# GloveBoard.net
KiCad netlist of a schematic drawn in EAGLE
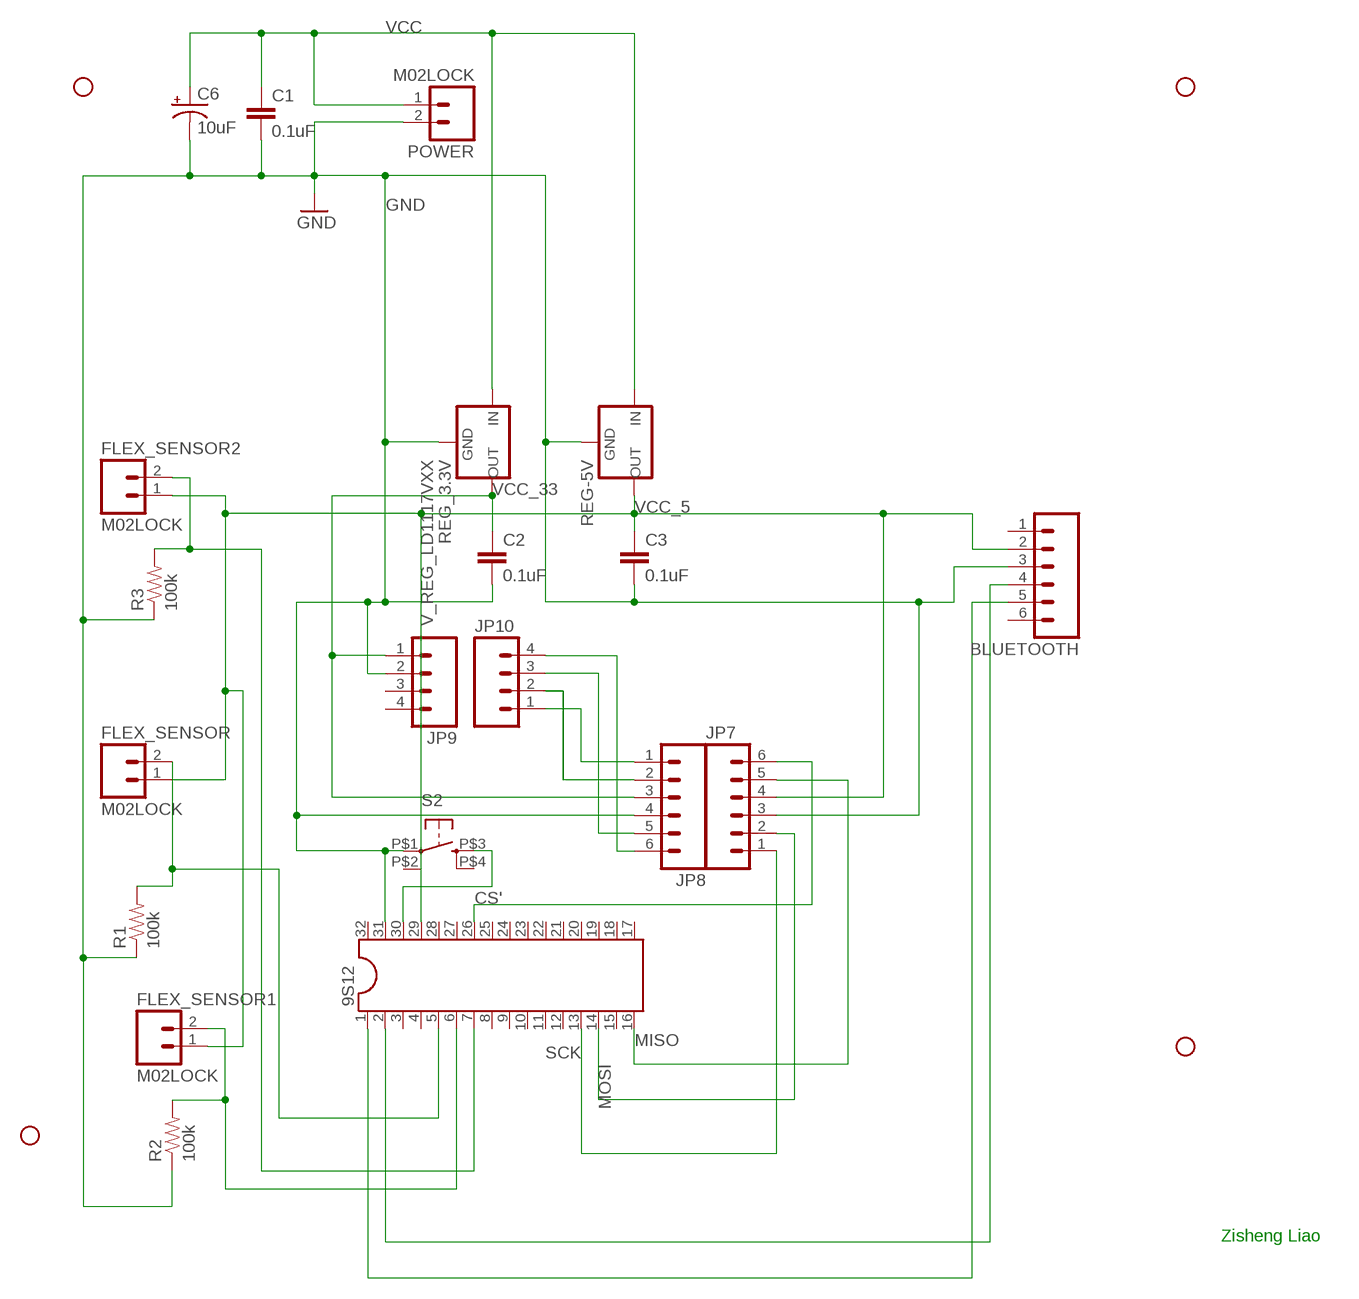
[diagram p0: schematic, sheet 1]

(export (version "E")
  (design (tool "Eeschema 10.0.6"))
  (components
    (comp (ref "9S12")
      (value "DIL32")
      (footprint "eagle-import:DIL32")
      (libsource (lib "eagle-import") (part "DIL32"))
    )
    (comp (ref "BLUETOOTH")
      (value "M06LOCK_LONGPADS")
      (footprint "eagle-import:1X06_LOCK_LONGPADS")
      (libsource (lib "eagle-import") (part "M06LOCK_LONGPADS"))
    )
    (comp (ref "C1")
      (value "0.1uF")
      (footprint "eagle-import:CAP-PTH-SMALL-KIT")
      (libsource (lib "eagle-import") (part "0.1UF-50V-20%(PTH)KIT-EZ"))
    )
    (comp (ref "C2")
      (value "0.1uF")
      (footprint "eagle-import:CAP-PTH-SMALL-KIT")
      (libsource (lib "eagle-import") (part "0.1UF-50V-20%(PTH)KIT-EZ"))
    )
    (comp (ref "C3")
      (value "0.1uF")
      (footprint "eagle-import:CAP-PTH-SMALL-KIT")
      (libsource (lib "eagle-import") (part "0.1UF-50V-20%(PTH)KIT-EZ"))
    )
    (comp (ref "C6")
      (value "10uF")
      (footprint "eagle-import:CPOL-RADIAL-10UF-25V")
      (libsource (lib "eagle-import") (part "CAP_POLPTH2"))
    )
    (comp (ref "FLEX_SENSOR")
      (value "M02LOCK")
      (footprint "eagle-import:1X02_LOCK")
      (libsource (lib "eagle-import") (part "M02LOCK"))
    )
    (comp (ref "FLEX_SENSOR1")
      (value "M02LOCK")
      (footprint "eagle-import:1X02_LOCK")
      (libsource (lib "eagle-import") (part "M02LOCK"))
    )
    (comp (ref "FLEX_SENSOR2")
      (value "M02LOCK")
      (footprint "eagle-import:1X02_LOCK")
      (libsource (lib "eagle-import") (part "M02LOCK"))
    )
    (comp (ref "JP7")
      (value "M06LOCK_LONGPADS")
      (footprint "eagle-import:1X06_LOCK_LONGPADS")
      (libsource (lib "eagle-import") (part "M06LOCK_LONGPADS"))
    )
    (comp (ref "JP8")
      (value "M06LOCK_LONGPADS")
      (footprint "eagle-import:1X06_LOCK_LONGPADS")
      (libsource (lib "eagle-import") (part "M06LOCK_LONGPADS"))
    )
    (comp (ref "JP9")
      (value "M04PTH")
      (footprint "eagle-import:1X04")
      (libsource (lib "eagle-import") (part "M04PTH"))
    )
    (comp (ref "JP10")
      (value "M04PTH")
      (footprint "eagle-import:1X04")
      (libsource (lib "eagle-import") (part "M04PTH"))
    )
    (comp (ref "POWER")
      (value "M02LOCK")
      (footprint "eagle-import:1X02_LOCK")
      (libsource (lib "eagle-import") (part "M02LOCK"))
    )
    (comp (ref "R1")
      (value "100k")
      (footprint "eagle-import:AXIAL-0.3-KIT")
      (libsource (lib "eagle-import") (part "10KOHM1/6W5%(PTH)KIT"))
    )
    (comp (ref "R2")
      (value "100k")
      (footprint "eagle-import:AXIAL-0.3-KIT")
      (libsource (lib "eagle-import") (part "10KOHM1/6W5%(PTH)KIT"))
    )
    (comp (ref "R3")
      (value "100k")
      (footprint "eagle-import:AXIAL-0.3-KIT")
      (libsource (lib "eagle-import") (part "10KOHM1/6W5%(PTH)KIT"))
    )
    (comp (ref "REG-5V")
      (value "V_REG_78XX-TO-220")
      (footprint "eagle-import:TO-220-ALT")
      (libsource (lib "eagle-import") (part "V_REG_78XX-TO-220"))
    )
    (comp (ref "REG_3.3V")
      (value "V_REG_LD1117VXX")
      (footprint "eagle-import:78XXL")
      (libsource (lib "eagle-import") (part "V_REG_LD1117VXX"))
    )
    (comp (ref "S2")
      (value "TAC_SWITCHKSA_SEALED")
      (footprint "eagle-import:KSA_SEALED_TAC_SWITCH")
      (libsource (lib "eagle-import") (part "TAC_SWITCHKSA_SEALED"))
    )
    (comp (ref "STANDOFF1")
      (value "STAND-OFF")
      (footprint "eagle-import:STAND-OFF")
      (libsource (lib "eagle-import") (part "STAND-OFF"))
    )
    (comp (ref "STANDOFF2")
      (value "STAND-OFF")
      (footprint "eagle-import:STAND-OFF")
      (libsource (lib "eagle-import") (part "STAND-OFF"))
    )
    (comp (ref "STANDOFF3")
      (value "STAND-OFF")
      (footprint "eagle-import:STAND-OFF")
      (libsource (lib "eagle-import") (part "STAND-OFF"))
    )
    (comp (ref "STANDOFF4")
      (value "STAND-OFF")
      (footprint "eagle-import:STAND-OFF")
      (libsource (lib "eagle-import") (part "STAND-OFF"))
    )
  )
  (nets
    (net (code "1") (name "/CS'") (class "Default")
      (node (ref "9S12") (pin "26") (pinfunction "26_26") (pintype "passive"))
      (node (ref "JP7") (pin "6") (pinfunction "6_6") (pintype "passive"))
    )
    (net (code "2") (name "/MISO") (class "Default")
      (node (ref "9S12") (pin "16") (pinfunction "16_16") (pintype "passive"))
      (node (ref "JP7") (pin "5") (pinfunction "5_5") (pintype "passive"))
    )
    (net (code "3") (name "/MOSI") (class "Default")
      (node (ref "9S12") (pin "14") (pinfunction "14_14") (pintype "passive"))
      (node (ref "JP7") (pin "2") (pinfunction "2_2") (pintype "passive"))
    )
    (net (code "4") (name "/SCK") (class "Default")
      (node (ref "9S12") (pin "13") (pinfunction "13_13") (pintype "passive"))
      (node (ref "JP7") (pin "1") (pinfunction "1_1") (pintype "passive"))
    )
    (net (code "5") (name "/VCC") (class "Default")
      (node (ref "C1") (pin "1") (pinfunction "1_1") (pintype "passive"))
      (node (ref "C6") (pin "1") (pinfunction "+_1") (pintype "passive"))
      (node (ref "POWER") (pin "1") (pinfunction "1_1") (pintype "passive"))
      (node (ref "REG-5V") (pin "IN") (pinfunction "IN_IN") (pintype "input"))
      (node (ref "REG_3.3V") (pin "OUT") (pinfunction "IN_OUT") (pintype "input"))
    )
    (net (code "6") (name "/VCC_5") (class "Default")
      (node (ref "9S12") (pin "29") (pinfunction "29_29") (pintype "passive"))
      (node (ref "BLUETOOTH") (pin "2") (pinfunction "2_2") (pintype "passive"))
      (node (ref "C3") (pin "1") (pinfunction "1_1") (pintype "passive"))
      (node (ref "FLEX_SENSOR") (pin "1") (pinfunction "1_1") (pintype "passive"))
      (node (ref "FLEX_SENSOR1") (pin "1") (pinfunction "1_1") (pintype "passive"))
      (node (ref "FLEX_SENSOR2") (pin "1") (pinfunction "1_1") (pintype "passive"))
      (node (ref "JP7") (pin "4") (pinfunction "4_4") (pintype "passive"))
      (node (ref "REG-5V") (pin "OUT") (pinfunction "OUT_OUT") (pintype "output"))
    )
    (net (code "7") (name "/VCC_33") (class "Default")
      (node (ref "C2") (pin "1") (pinfunction "1_1") (pintype "passive"))
      (node (ref "JP8") (pin "3") (pinfunction "3_3") (pintype "passive"))
      (node (ref "JP9") (pin "1") (pinfunction "1_1") (pintype "passive"))
      (node (ref "REG_3.3V") (pin "GND") (pinfunction "OUT_GND") (pintype "output"))
    )
    (net (code "8") (name "GND") (class "Default")
      (node (ref "9S12") (pin "31") (pinfunction "31_31") (pintype "passive"))
      (node (ref "BLUETOOTH") (pin "3") (pinfunction "3_3") (pintype "passive"))
      (node (ref "C1") (pin "2") (pinfunction "2_2") (pintype "passive"))
      (node (ref "C2") (pin "2") (pinfunction "2_2") (pintype "passive"))
      (node (ref "C3") (pin "2") (pinfunction "2_2") (pintype "passive"))
      (node (ref "C6") (pin "2") (pinfunction "-_2") (pintype "passive"))
      (node (ref "JP7") (pin "3") (pinfunction "3_3") (pintype "passive"))
      (node (ref "JP8") (pin "4") (pinfunction "4_4") (pintype "passive"))
      (node (ref "JP9") (pin "2") (pinfunction "2_2") (pintype "passive"))
      (node (ref "POWER") (pin "2") (pinfunction "2_2") (pintype "passive"))
      (node (ref "R1") (pin "P$1") (pinfunction "1_P$1") (pintype "passive"))
      (node (ref "R2") (pin "P$1") (pinfunction "1_P$1") (pintype "passive"))
      (node (ref "R3") (pin "P$1") (pinfunction "1_P$1") (pintype "passive"))
      (node (ref "REG-5V") (pin "GND") (pinfunction "GND_GND") (pintype "input"))
      (node (ref "REG_3.3V") (pin "IN") (pinfunction "GND_IN") (pintype "input"))
      (node (ref "S2") (pin "P$1") (pinfunction "1_P$1") (pintype "passive"))
    )
    (net (code "9") (name "Net-(9S12-Pad1)") (class "Default")
      (node (ref "9S12") (pin "1") (pinfunction "1_1") (pintype "passive"))
      (node (ref "BLUETOOTH") (pin "5") (pinfunction "5_5") (pintype "passive"))
    )
    (net (code "10") (name "Net-(9S12-Pad2)") (class "Default")
      (node (ref "9S12") (pin "2") (pinfunction "2_2") (pintype "passive"))
      (node (ref "BLUETOOTH") (pin "4") (pinfunction "4_4") (pintype "passive"))
    )
    (net (code "11") (name "Net-(JP10-Pad1)") (class "Default")
      (node (ref "JP10") (pin "1") (pinfunction "1_1") (pintype "passive"))
      (node (ref "JP8") (pin "1") (pinfunction "1_1") (pintype "passive"))
    )
    (net (code "12") (name "Net-(JP10-Pad2)") (class "Default")
      (node (ref "JP10") (pin "2") (pinfunction "2_2") (pintype "passive"))
      (node (ref "JP8") (pin "2") (pinfunction "2_2") (pintype "passive"))
    )
    (net (code "13") (name "Net-(JP10-Pad3)") (class "Default")
      (node (ref "JP10") (pin "3") (pinfunction "3_3") (pintype "passive"))
      (node (ref "JP8") (pin "5") (pinfunction "5_5") (pintype "passive"))
    )
    (net (code "14") (name "Net-(JP10-Pad4)") (class "Default")
      (node (ref "JP10") (pin "4") (pinfunction "4_4") (pintype "passive"))
      (node (ref "JP8") (pin "6") (pinfunction "6_6") (pintype "passive"))
    )
    (net (code "15") (name "Net-(R1-2)") (class "Default")
      (node (ref "9S12") (pin "5") (pinfunction "5_5") (pintype "passive"))
      (node (ref "FLEX_SENSOR") (pin "2") (pinfunction "2_2") (pintype "passive"))
      (node (ref "R1") (pin "P$2") (pinfunction "2_P$2") (pintype "passive"))
    )
    (net (code "16") (name "Net-(R2-2)") (class "Default")
      (node (ref "9S12") (pin "6") (pinfunction "6_6") (pintype "passive"))
      (node (ref "FLEX_SENSOR1") (pin "2") (pinfunction "2_2") (pintype "passive"))
      (node (ref "R2") (pin "P$2") (pinfunction "2_P$2") (pintype "passive"))
    )
    (net (code "17") (name "Net-(R3-2)") (class "Default")
      (node (ref "9S12") (pin "7") (pinfunction "7_7") (pintype "passive"))
      (node (ref "FLEX_SENSOR2") (pin "2") (pinfunction "2_2") (pintype "passive"))
      (node (ref "R3") (pin "P$2") (pinfunction "2_P$2") (pintype "passive"))
    )
    (net (code "18") (name "Net-(S2-3)") (class "Default")
      (node (ref "9S12") (pin "30") (pinfunction "30_30") (pintype "passive"))
      (node (ref "S2") (pin "P$3") (pinfunction "3_P$3") (pintype "passive"))
    )
    (net (code "19") (name "unconnected-(9S12-Pad3)") (class "Default")
      (node (ref "9S12") (pin "3") (pinfunction "3_3") (pintype "passive"))
    )
    (net (code "20") (name "unconnected-(9S12-Pad4)") (class "Default")
      (node (ref "9S12") (pin "4") (pinfunction "4_4") (pintype "passive"))
    )
    (net (code "21") (name "unconnected-(9S12-Pad8)") (class "Default")
      (node (ref "9S12") (pin "8") (pinfunction "8_8") (pintype "passive"))
    )
    (net (code "22") (name "unconnected-(9S12-Pad9)") (class "Default")
      (node (ref "9S12") (pin "9") (pinfunction "9_9") (pintype "passive"))
    )
    (net (code "23") (name "unconnected-(9S12-Pad10)") (class "Default")
      (node (ref "9S12") (pin "10") (pinfunction "10_10") (pintype "passive"))
    )
    (net (code "24") (name "unconnected-(9S12-Pad11)") (class "Default")
      (node (ref "9S12") (pin "11") (pinfunction "11_11") (pintype "passive"))
    )
    (net (code "25") (name "unconnected-(9S12-Pad12)") (class "Default")
      (node (ref "9S12") (pin "12") (pinfunction "12_12") (pintype "passive"))
    )
    (net (code "26") (name "unconnected-(9S12-Pad15)") (class "Default")
      (node (ref "9S12") (pin "15") (pinfunction "15_15") (pintype "passive"))
    )
    (net (code "27") (name "unconnected-(9S12-Pad17)") (class "Default")
      (node (ref "9S12") (pin "17") (pinfunction "17_17") (pintype "passive"))
    )
    (net (code "28") (name "unconnected-(9S12-Pad18)") (class "Default")
      (node (ref "9S12") (pin "18") (pinfunction "18_18") (pintype "passive"))
    )
    (net (code "29") (name "unconnected-(9S12-Pad19)") (class "Default")
      (node (ref "9S12") (pin "19") (pinfunction "19_19") (pintype "passive"))
    )
    (net (code "30") (name "unconnected-(9S12-Pad20)") (class "Default")
      (node (ref "9S12") (pin "20") (pinfunction "20_20") (pintype "passive"))
    )
    (net (code "31") (name "unconnected-(9S12-Pad21)") (class "Default")
      (node (ref "9S12") (pin "21") (pinfunction "21_21") (pintype "passive"))
    )
    (net (code "32") (name "unconnected-(9S12-Pad22)") (class "Default")
      (node (ref "9S12") (pin "22") (pinfunction "22_22") (pintype "passive"))
    )
    (net (code "33") (name "unconnected-(9S12-Pad23)") (class "Default")
      (node (ref "9S12") (pin "23") (pinfunction "23_23") (pintype "passive"))
    )
    (net (code "34") (name "unconnected-(9S12-Pad24)") (class "Default")
      (node (ref "9S12") (pin "24") (pinfunction "24_24") (pintype "passive"))
    )
    (net (code "35") (name "unconnected-(9S12-Pad25)") (class "Default")
      (node (ref "9S12") (pin "25") (pinfunction "25_25") (pintype "passive"))
    )
    (net (code "36") (name "unconnected-(9S12-Pad27)") (class "Default")
      (node (ref "9S12") (pin "27") (pinfunction "27_27") (pintype "passive"))
    )
    (net (code "37") (name "unconnected-(9S12-Pad28)") (class "Default")
      (node (ref "9S12") (pin "28") (pinfunction "28_28") (pintype "passive"))
    )
    (net (code "38") (name "unconnected-(9S12-Pad32)") (class "Default")
      (node (ref "9S12") (pin "32") (pinfunction "32_32") (pintype "passive"))
    )
    (net (code "39") (name "unconnected-(BLUETOOTH-Pad1)") (class "Default")
      (node (ref "BLUETOOTH") (pin "1") (pinfunction "1_1") (pintype "passive"))
    )
    (net (code "40") (name "unconnected-(BLUETOOTH-Pad6)") (class "Default")
      (node (ref "BLUETOOTH") (pin "6") (pinfunction "6_6") (pintype "passive"))
    )
    (net (code "41") (name "unconnected-(JP9-Pad3)") (class "Default")
      (node (ref "JP9") (pin "3") (pinfunction "3_3") (pintype "passive"))
    )
    (net (code "42") (name "unconnected-(JP9-Pad4)") (class "Default")
      (node (ref "JP9") (pin "4") (pinfunction "4_4") (pintype "passive"))
    )
    (net (code "43") (name "unconnected-(S2-2-PadP$2)") (class "Default")
      (node (ref "S2") (pin "P$2") (pinfunction "2_P$2") (pintype "passive"))
    )
    (net (code "44") (name "unconnected-(S2-4-PadP$4)") (class "Default")
      (node (ref "S2") (pin "P$4") (pinfunction "4_P$4") (pintype "passive"))
    )
  )
)
